# breadboard-mcp2515.net
KiCad netlist of a schematic drawn in EAGLE
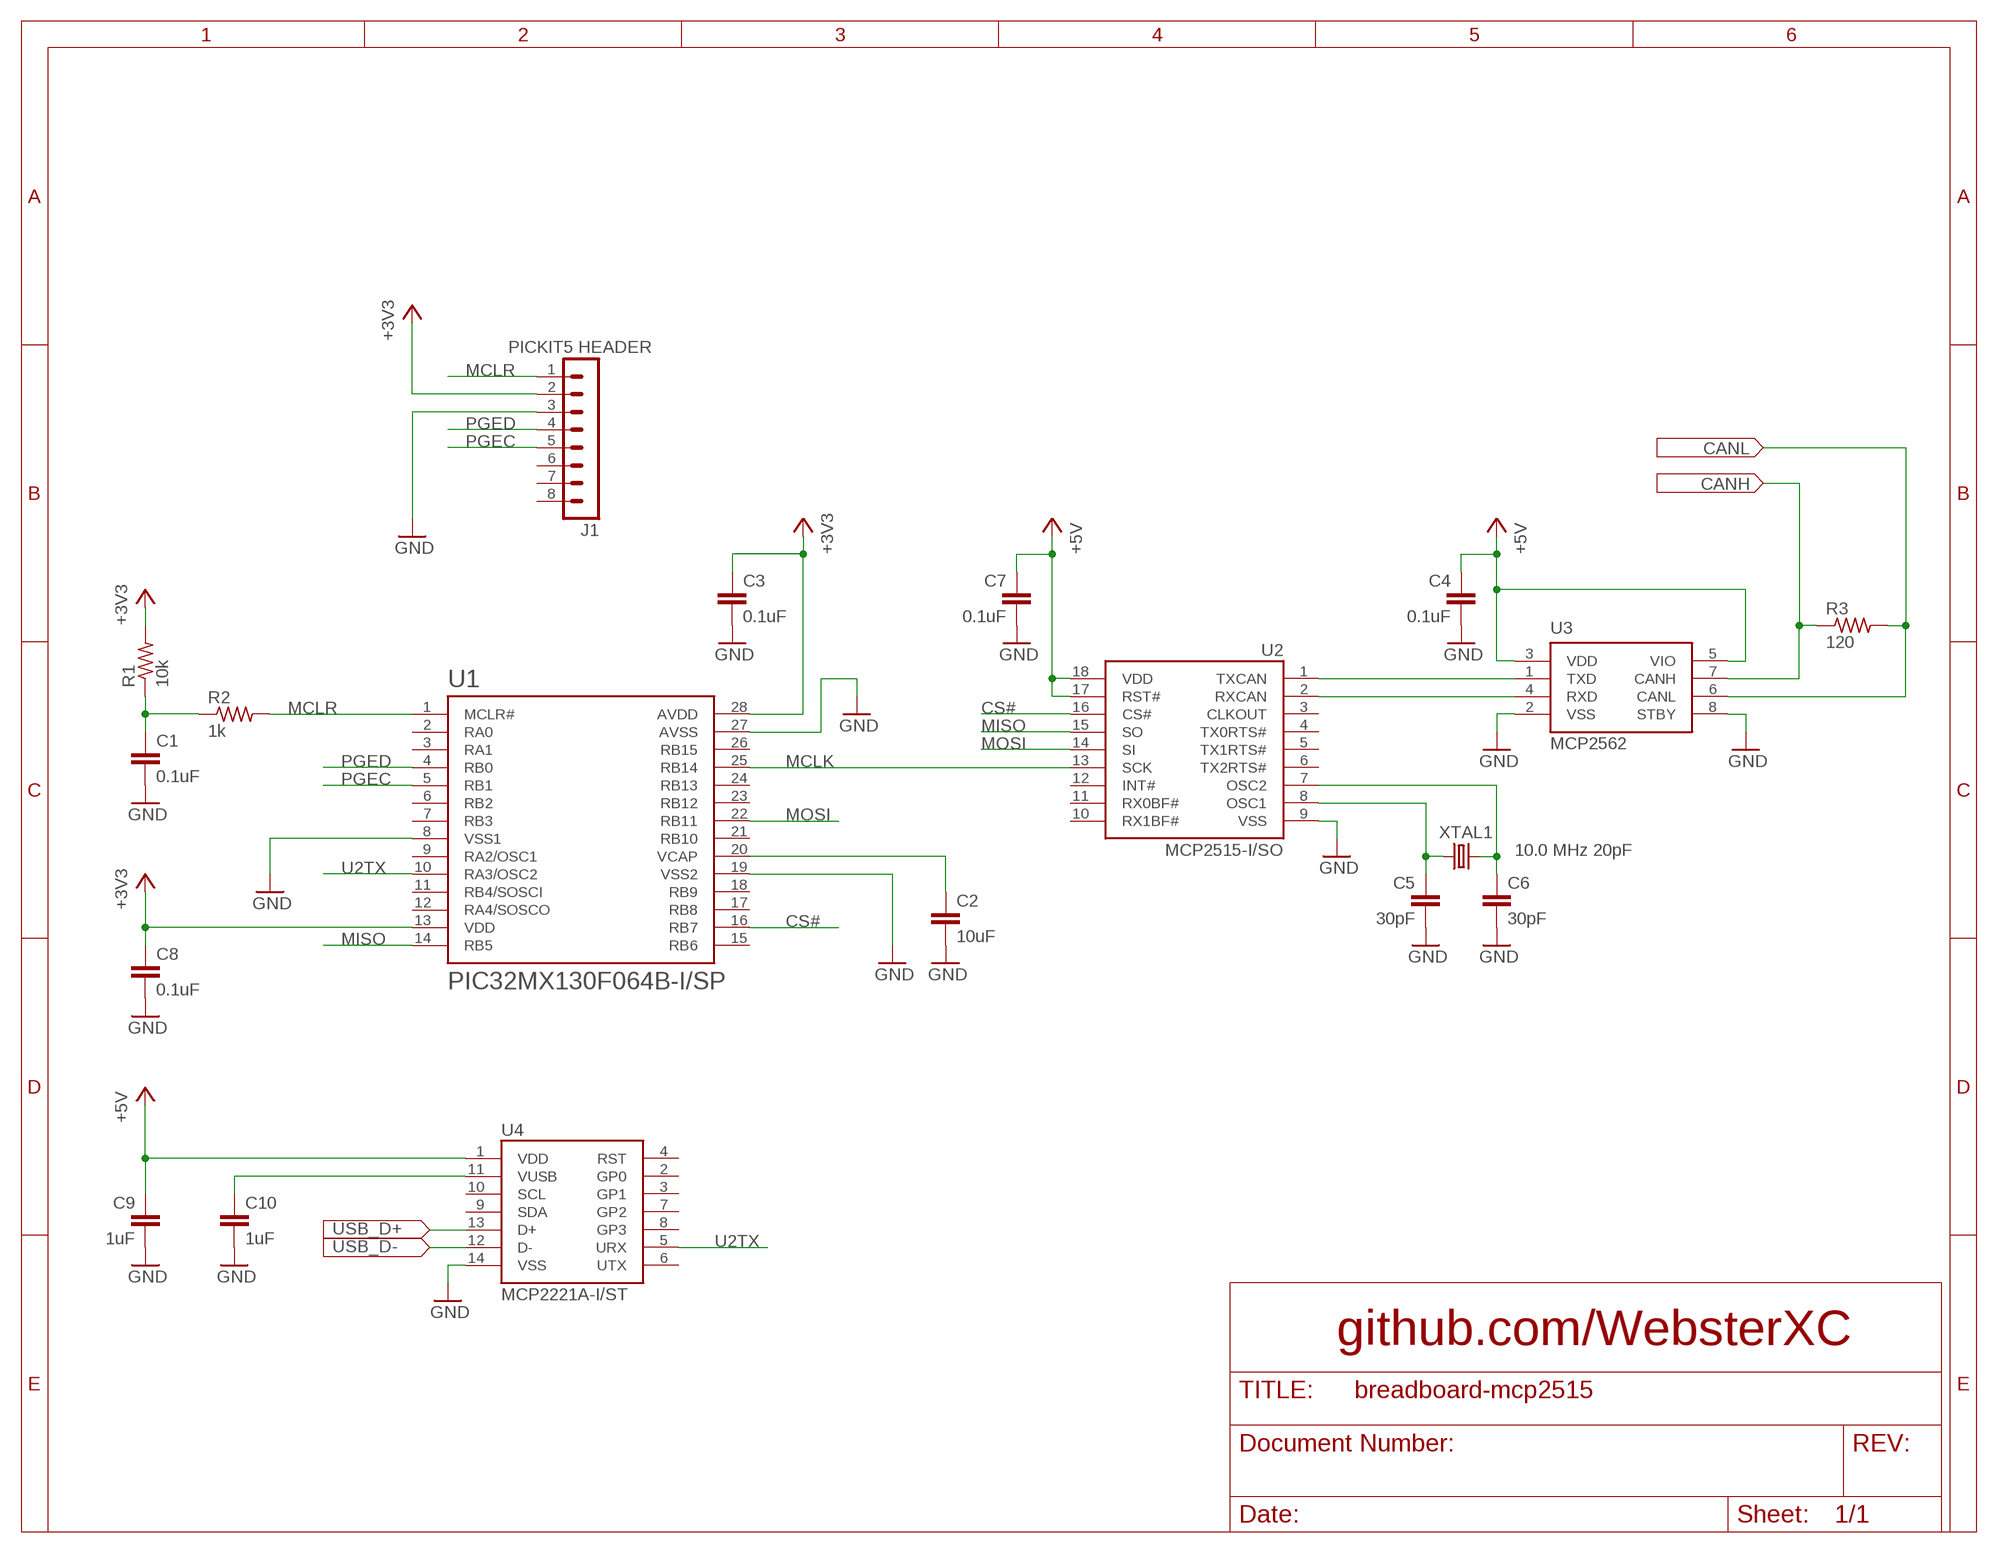
[diagram p0: schematic, sheet 1]

(export (version "E")
  (design (tool "Eeschema 10.0.6"))
  (components
    (comp (ref "C1")
      (value "0.1uF")
      (footprint "eagle-import:C0603")
      (libsource (lib "eagle-import") (part "C-EUC0603"))
    )
    (comp (ref "C2")
      (value "10uF")
      (footprint "eagle-import:C0603")
      (libsource (lib "eagle-import") (part "C-EUC0603"))
    )
    (comp (ref "C3")
      (value "0.1uF")
      (footprint "eagle-import:C0603")
      (libsource (lib "eagle-import") (part "C-EUC0603"))
    )
    (comp (ref "C4")
      (value "0.1uF")
      (footprint "eagle-import:C0603")
      (libsource (lib "eagle-import") (part "C-EUC0603"))
    )
    (comp (ref "C5")
      (value "30pF")
      (footprint "eagle-import:C0603")
      (libsource (lib "eagle-import") (part "C-EUC0603"))
    )
    (comp (ref "C6")
      (value "30pF")
      (footprint "eagle-import:C0603")
      (libsource (lib "eagle-import") (part "C-EUC0603"))
    )
    (comp (ref "C7")
      (value "0.1uF")
      (footprint "eagle-import:C0603")
      (libsource (lib "eagle-import") (part "C-EUC0603"))
    )
    (comp (ref "C8")
      (value "0.1uF")
      (footprint "eagle-import:C0603")
      (libsource (lib "eagle-import") (part "C-EUC0603"))
    )
    (comp (ref "C9")
      (value "1uF")
      (footprint "eagle-import:C0603")
      (libsource (lib "eagle-import") (part "C-EUC0603"))
    )
    (comp (ref "C10")
      (value "1uF")
      (footprint "eagle-import:C0603")
      (libsource (lib "eagle-import") (part "C-EUC0603"))
    )
    (comp (ref "J1")
      (value "PICKIT5 HEADER")
      (footprint "eagle-import:MA08-1")
      (libsource (lib "eagle-import") (part "MA08-1"))
    )
    (comp (ref "R1")
      (value "10k")
      (footprint "eagle-import:R0603")
      (libsource (lib "eagle-import") (part "R-US_R0603"))
    )
    (comp (ref "R2")
      (value "1k")
      (footprint "eagle-import:R0603")
      (libsource (lib "eagle-import") (part "R-US_R0603"))
    )
    (comp (ref "R3")
      (value "120")
      (footprint "eagle-import:R0603")
      (libsource (lib "eagle-import") (part "R-US_R0603"))
    )
    (comp (ref "U1")
      (value "PIC32MX130F064B-I/SP")
      (footprint "eagle-import:SSOP28")
      (libsource (lib "eagle-import") (part "PIC32MX130F"))
    )
    (comp (ref "U2")
      (value "MCP2515-I/SO")
      (footprint "eagle-import:SOIC18L")
      (libsource (lib "eagle-import") (part "MCP2515-I/SO"))
    )
    (comp (ref "U3")
      (value "MCP2562")
      (footprint "eagle-import:SOIC8")
      (libsource (lib "eagle-import") (part "MCP2562"))
    )
    (comp (ref "U4")
      (value "MCP2221A-I/ST")
      (footprint "eagle-import:TSSOP14")
      (libsource (lib "eagle-import") (part "MCP2221A-I/ST"))
    )
    (comp (ref "XTAL1")
      (value "10.0 MHz 20pF")
      (footprint "eagle-import:86SMX")
      (libsource (lib "eagle-import") (part "CRYSTAL68SMX"))
    )
  )
  (nets
    (net (code "1") (name "+3V3") (class "Default")
      (node (ref "C3") (pin "1") (pinfunction "1_1") (pintype "passive"))
      (node (ref "C8") (pin "1") (pinfunction "1_1") (pintype "passive"))
      (node (ref "J1") (pin "2") (pinfunction "2_2") (pintype "passive"))
      (node (ref "R1") (pin "2") (pinfunction "2_2") (pintype "passive"))
      (node (ref "U1") (pin "13") (pinfunction "VDD_13") (pintype "bidirectional"))
      (node (ref "U1") (pin "28") (pinfunction "AVDD_28") (pintype "bidirectional"))
    )
    (net (code "2") (name "+5V") (class "Default")
      (node (ref "C4") (pin "1") (pinfunction "1_1") (pintype "passive"))
      (node (ref "C7") (pin "1") (pinfunction "1_1") (pintype "passive"))
      (node (ref "C9") (pin "1") (pinfunction "1_1") (pintype "passive"))
      (node (ref "U2") (pin "17") (pinfunction "RST#_17") (pintype "bidirectional"))
      (node (ref "U2") (pin "18") (pinfunction "VDD_18") (pintype "bidirectional"))
      (node (ref "U3") (pin "3") (pinfunction "VDD_3") (pintype "bidirectional"))
      (node (ref "U3") (pin "5") (pinfunction "VIO_5") (pintype "bidirectional"))
      (node (ref "U4") (pin "1") (pinfunction "VDD_1") (pintype "bidirectional"))
    )
    (net (code "3") (name "/CS#") (class "Default")
      (node (ref "U1") (pin "16") (pinfunction "RB7_16") (pintype "bidirectional"))
      (node (ref "U2") (pin "16") (pinfunction "CS#_16") (pintype "bidirectional"))
    )
    (net (code "4") (name "/MCLK") (class "Default")
      (node (ref "U1") (pin "25") (pinfunction "RB14_25") (pintype "bidirectional"))
      (node (ref "U2") (pin "13") (pinfunction "SCK_13") (pintype "bidirectional"))
    )
    (net (code "5") (name "/MCLR") (class "Default")
      (node (ref "J1") (pin "1") (pinfunction "1_1") (pintype "passive"))
      (node (ref "R2") (pin "2") (pinfunction "2_2") (pintype "passive"))
      (node (ref "U1") (pin "1") (pinfunction "MCLR#_1") (pintype "bidirectional"))
    )
    (net (code "6") (name "/MISO") (class "Default")
      (node (ref "U1") (pin "14") (pinfunction "RB5_14") (pintype "bidirectional"))
      (node (ref "U2") (pin "15") (pinfunction "SO_15") (pintype "bidirectional"))
    )
    (net (code "7") (name "/MOSI") (class "Default")
      (node (ref "U1") (pin "22") (pinfunction "RB11_22") (pintype "bidirectional"))
      (node (ref "U2") (pin "14") (pinfunction "SI_14") (pintype "bidirectional"))
    )
    (net (code "8") (name "/PGEC") (class "Default")
      (node (ref "J1") (pin "5") (pinfunction "5_5") (pintype "passive"))
      (node (ref "U1") (pin "5") (pinfunction "RB1_5") (pintype "bidirectional"))
    )
    (net (code "9") (name "/PGED") (class "Default")
      (node (ref "J1") (pin "4") (pinfunction "4_4") (pintype "passive"))
      (node (ref "U1") (pin "4") (pinfunction "RB0_4") (pintype "bidirectional"))
    )
    (net (code "10") (name "/U2TX") (class "Default")
      (node (ref "U1") (pin "10") (pinfunction "RA3/OSC2_10") (pintype "bidirectional"))
      (node (ref "U4") (pin "5") (pinfunction "URX_5") (pintype "bidirectional"))
    )
    (net (code "11") (name "GND") (class "Default")
      (node (ref "C1") (pin "2") (pinfunction "2_2") (pintype "passive"))
      (node (ref "C10") (pin "2") (pinfunction "2_2") (pintype "passive"))
      (node (ref "C2") (pin "2") (pinfunction "2_2") (pintype "passive"))
      (node (ref "C3") (pin "2") (pinfunction "2_2") (pintype "passive"))
      (node (ref "C4") (pin "2") (pinfunction "2_2") (pintype "passive"))
      (node (ref "C5") (pin "2") (pinfunction "2_2") (pintype "passive"))
      (node (ref "C6") (pin "2") (pinfunction "2_2") (pintype "passive"))
      (node (ref "C7") (pin "2") (pinfunction "2_2") (pintype "passive"))
      (node (ref "C8") (pin "2") (pinfunction "2_2") (pintype "passive"))
      (node (ref "C9") (pin "2") (pinfunction "2_2") (pintype "passive"))
      (node (ref "J1") (pin "3") (pinfunction "3_3") (pintype "passive"))
      (node (ref "U1") (pin "19") (pinfunction "VSS2_19") (pintype "bidirectional"))
      (node (ref "U1") (pin "27") (pinfunction "AVSS_27") (pintype "bidirectional"))
      (node (ref "U1") (pin "8") (pinfunction "VSS1_8") (pintype "bidirectional"))
      (node (ref "U2") (pin "9") (pinfunction "VSS_9") (pintype "bidirectional"))
      (node (ref "U3") (pin "2") (pinfunction "VSS_2") (pintype "bidirectional"))
      (node (ref "U3") (pin "8") (pinfunction "STBY_8") (pintype "bidirectional"))
      (node (ref "U4") (pin "14") (pinfunction "VSS_14") (pintype "bidirectional"))
    )
    (net (code "12") (name "Net-(C1-Pad1)") (class "Default")
      (node (ref "C1") (pin "1") (pinfunction "1_1") (pintype "passive"))
      (node (ref "R1") (pin "1") (pinfunction "1_1") (pintype "passive"))
      (node (ref "R2") (pin "1") (pinfunction "1_1") (pintype "passive"))
    )
    (net (code "13") (name "Net-(U1-VCAP)") (class "Default")
      (node (ref "C2") (pin "1") (pinfunction "1_1") (pintype "passive"))
      (node (ref "U1") (pin "20") (pinfunction "VCAP_20") (pintype "bidirectional"))
    )
    (net (code "14") (name "Net-(U2-OSC1)") (class "Default")
      (node (ref "C5") (pin "1") (pinfunction "1_1") (pintype "passive"))
      (node (ref "U2") (pin "8") (pinfunction "OSC1_8") (pintype "bidirectional"))
      (node (ref "XTAL1") (pin "1") (pinfunction "1_1") (pintype "passive"))
    )
    (net (code "15") (name "Net-(U2-OSC2)") (class "Default")
      (node (ref "C6") (pin "1") (pinfunction "1_1") (pintype "passive"))
      (node (ref "U2") (pin "7") (pinfunction "OSC2_7") (pintype "bidirectional"))
      (node (ref "XTAL1") (pin "4") (pinfunction "2_4") (pintype "passive"))
    )
    (net (code "16") (name "Net-(U2-RXCAN)") (class "Default")
      (node (ref "U2") (pin "2") (pinfunction "RXCAN_2") (pintype "bidirectional"))
      (node (ref "U3") (pin "4") (pinfunction "RXD_4") (pintype "bidirectional"))
    )
    (net (code "17") (name "Net-(U2-TXCAN)") (class "Default")
      (node (ref "U2") (pin "1") (pinfunction "TXCAN_1") (pintype "bidirectional"))
      (node (ref "U3") (pin "1") (pinfunction "TXD_1") (pintype "bidirectional"))
    )
    (net (code "18") (name "Net-(U3-CANH)") (class "Default")
      (node (ref "R3") (pin "1") (pinfunction "1_1") (pintype "passive"))
      (node (ref "U3") (pin "7") (pinfunction "CANH_7") (pintype "bidirectional"))
    )
    (net (code "19") (name "Net-(U3-CANL)") (class "Default")
      (node (ref "R3") (pin "2") (pinfunction "2_2") (pintype "passive"))
      (node (ref "U3") (pin "6") (pinfunction "CANL_6") (pintype "bidirectional"))
    )
    (net (code "20") (name "Net-(U4-VUSB)") (class "Default")
      (node (ref "C10") (pin "1") (pinfunction "1_1") (pintype "passive"))
      (node (ref "U4") (pin "11") (pinfunction "VUSB_11") (pintype "bidirectional"))
    )
    (net (code "21") (name "unconnected-(J1-Pad6)") (class "Default")
      (node (ref "J1") (pin "6") (pinfunction "6_6") (pintype "passive"))
    )
    (net (code "22") (name "unconnected-(J1-Pad7)") (class "Default")
      (node (ref "J1") (pin "7") (pinfunction "7_7") (pintype "passive"))
    )
    (net (code "23") (name "unconnected-(J1-Pad8)") (class "Default")
      (node (ref "J1") (pin "8") (pinfunction "8_8") (pintype "passive"))
    )
    (net (code "24") (name "unconnected-(U1-RA0-Pad2)") (class "Default")
      (node (ref "U1") (pin "2") (pinfunction "RA0_2") (pintype "bidirectional"))
    )
    (net (code "25") (name "unconnected-(U1-RA1-Pad3)") (class "Default")
      (node (ref "U1") (pin "3") (pinfunction "RA1_3") (pintype "bidirectional"))
    )
    (net (code "26") (name "unconnected-(U1-RA2{slash}OSC1-Pad9)") (class "Default")
      (node (ref "U1") (pin "9") (pinfunction "RA2/OSC1_9") (pintype "bidirectional"))
    )
    (net (code "27") (name "unconnected-(U1-RA4{slash}SOSCO-Pad12)") (class "Default")
      (node (ref "U1") (pin "12") (pinfunction "RA4/SOSCO_12") (pintype "bidirectional"))
    )
    (net (code "28") (name "unconnected-(U1-RB2-Pad6)") (class "Default")
      (node (ref "U1") (pin "6") (pinfunction "RB2_6") (pintype "bidirectional"))
    )
    (net (code "29") (name "unconnected-(U1-RB3-Pad7)") (class "Default")
      (node (ref "U1") (pin "7") (pinfunction "RB3_7") (pintype "bidirectional"))
    )
    (net (code "30") (name "unconnected-(U1-RB4{slash}SOSCI-Pad11)") (class "Default")
      (node (ref "U1") (pin "11") (pinfunction "RB4/SOSCI_11") (pintype "bidirectional"))
    )
    (net (code "31") (name "unconnected-(U1-RB6-Pad15)") (class "Default")
      (node (ref "U1") (pin "15") (pinfunction "RB6_15") (pintype "bidirectional"))
    )
    (net (code "32") (name "unconnected-(U1-RB8-Pad17)") (class "Default")
      (node (ref "U1") (pin "17") (pinfunction "RB8_17") (pintype "bidirectional"))
    )
    (net (code "33") (name "unconnected-(U1-RB9-Pad18)") (class "Default")
      (node (ref "U1") (pin "18") (pinfunction "RB9_18") (pintype "bidirectional"))
    )
    (net (code "34") (name "unconnected-(U1-RB10-Pad21)") (class "Default")
      (node (ref "U1") (pin "21") (pinfunction "RB10_21") (pintype "bidirectional"))
    )
    (net (code "35") (name "unconnected-(U1-RB12-Pad23)") (class "Default")
      (node (ref "U1") (pin "23") (pinfunction "RB12_23") (pintype "bidirectional"))
    )
    (net (code "36") (name "unconnected-(U1-RB13-Pad24)") (class "Default")
      (node (ref "U1") (pin "24") (pinfunction "RB13_24") (pintype "bidirectional"))
    )
    (net (code "37") (name "unconnected-(U1-RB15-Pad26)") (class "Default")
      (node (ref "U1") (pin "26") (pinfunction "RB15_26") (pintype "bidirectional"))
    )
    (net (code "38") (name "unconnected-(U2-CLKOUT-Pad3)") (class "Default")
      (node (ref "U2") (pin "3") (pinfunction "CLKOUT_3") (pintype "bidirectional"))
    )
    (net (code "39") (name "unconnected-(U2-INT#-Pad12)") (class "Default")
      (node (ref "U2") (pin "12") (pinfunction "INT#_12") (pintype "bidirectional"))
    )
    (net (code "40") (name "unconnected-(U2-RX0BF#-Pad11)") (class "Default")
      (node (ref "U2") (pin "11") (pinfunction "RX0BF#_11") (pintype "bidirectional"))
    )
    (net (code "41") (name "unconnected-(U2-RX1BF#-Pad10)") (class "Default")
      (node (ref "U2") (pin "10") (pinfunction "RX1BF#_10") (pintype "bidirectional"))
    )
    (net (code "42") (name "unconnected-(U2-TX0RTS#-Pad4)") (class "Default")
      (node (ref "U2") (pin "4") (pinfunction "TX0RTS#_4") (pintype "bidirectional"))
    )
    (net (code "43") (name "unconnected-(U2-TX1RTS#-Pad5)") (class "Default")
      (node (ref "U2") (pin "5") (pinfunction "TX1RTS#_5") (pintype "bidirectional"))
    )
    (net (code "44") (name "unconnected-(U2-TX2RTS#-Pad6)") (class "Default")
      (node (ref "U2") (pin "6") (pinfunction "TX2RTS#_6") (pintype "bidirectional"))
    )
    (net (code "45") (name "unconnected-(U4-D+-Pad13)") (class "Default")
      (node (ref "U4") (pin "13") (pinfunction "D+_13") (pintype "bidirectional"))
    )
    (net (code "46") (name "unconnected-(U4-D--Pad12)") (class "Default")
      (node (ref "U4") (pin "12") (pinfunction "D-_12") (pintype "bidirectional"))
    )
    (net (code "47") (name "unconnected-(U4-GP0-Pad2)") (class "Default")
      (node (ref "U4") (pin "2") (pinfunction "GP0_2") (pintype "bidirectional"))
    )
    (net (code "48") (name "unconnected-(U4-GP1-Pad3)") (class "Default")
      (node (ref "U4") (pin "3") (pinfunction "GP1_3") (pintype "bidirectional"))
    )
    (net (code "49") (name "unconnected-(U4-GP2-Pad7)") (class "Default")
      (node (ref "U4") (pin "7") (pinfunction "GP2_7") (pintype "bidirectional"))
    )
    (net (code "50") (name "unconnected-(U4-GP3-Pad8)") (class "Default")
      (node (ref "U4") (pin "8") (pinfunction "GP3_8") (pintype "bidirectional"))
    )
    (net (code "51") (name "unconnected-(U4-RST-Pad4)") (class "Default")
      (node (ref "U4") (pin "4") (pinfunction "RST_4") (pintype "bidirectional"))
    )
    (net (code "52") (name "unconnected-(U4-SCL-Pad10)") (class "Default")
      (node (ref "U4") (pin "10") (pinfunction "SCL_10") (pintype "bidirectional"))
    )
    (net (code "53") (name "unconnected-(U4-SDA-Pad9)") (class "Default")
      (node (ref "U4") (pin "9") (pinfunction "SDA_9") (pintype "bidirectional"))
    )
    (net (code "54") (name "unconnected-(U4-UTX-Pad6)") (class "Default")
      (node (ref "U4") (pin "6") (pinfunction "UTX_6") (pintype "bidirectional"))
    )
  )
)
